# NLQHD-SATA_Rev_2.net
KiCad netlist of a schematic drawn in EAGLE
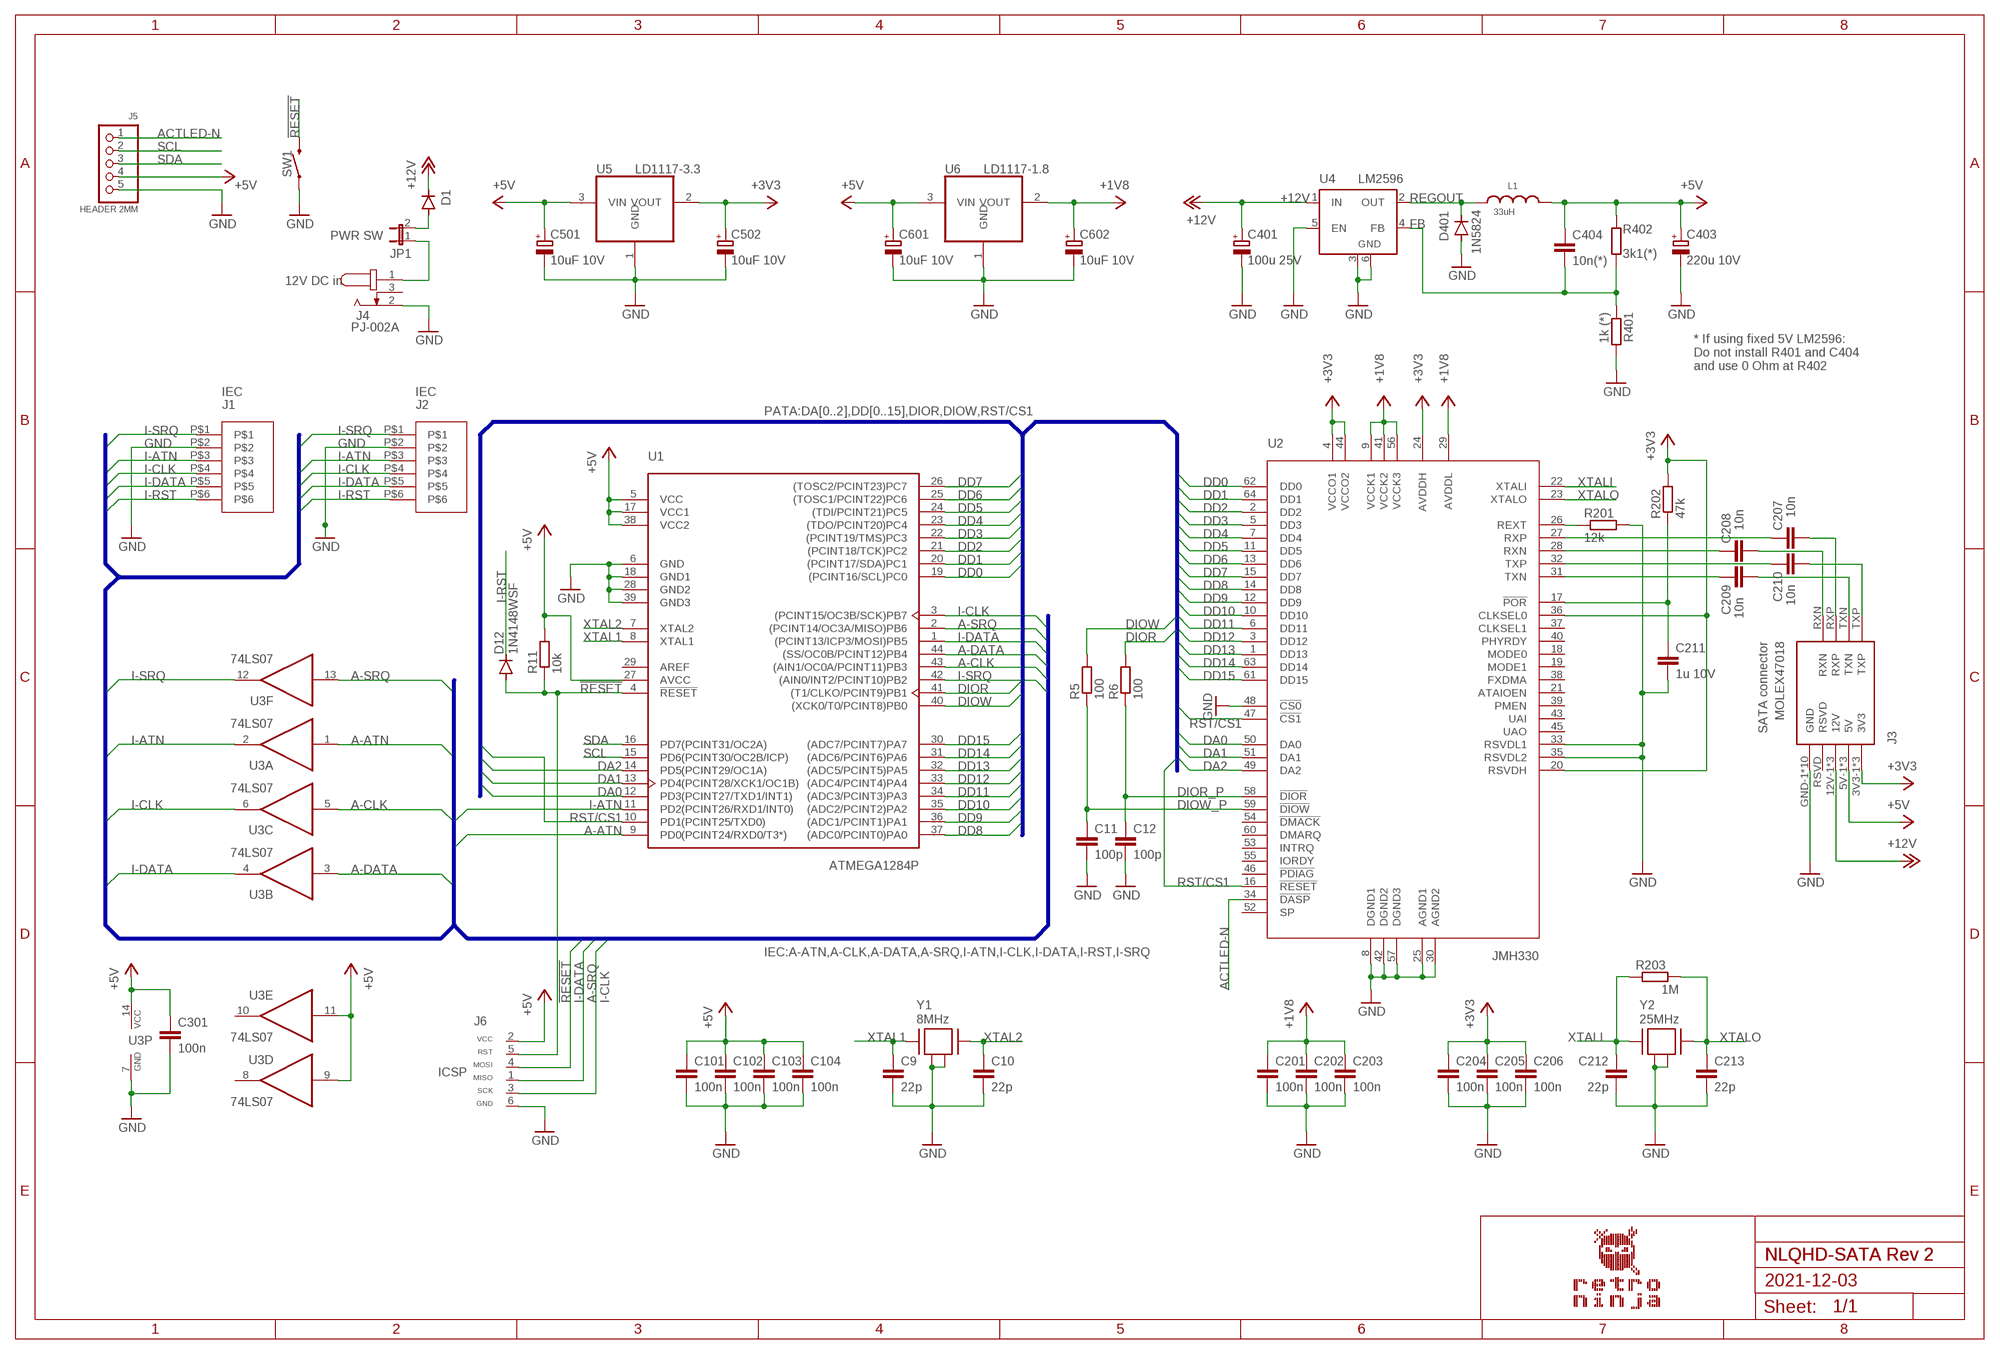
[diagram p0: schematic, sheet 1]

(export (version "E")
  (design (tool "Eeschema 10.0.6"))
  (components
    (comp (ref "C9")
      (value "22p")
      (footprint "eagle-import:C0805")
      (libsource (lib "eagle-import") (part "C-EUC0805"))
    )
    (comp (ref "C10")
      (value "22p")
      (footprint "eagle-import:C0805")
      (libsource (lib "eagle-import") (part "C-EUC0805"))
    )
    (comp (ref "C11")
      (value "100p")
      (footprint "eagle-import:C0805")
      (libsource (lib "eagle-import") (part "C-EUC0805"))
    )
    (comp (ref "C12")
      (value "100p")
      (footprint "eagle-import:C0805")
      (libsource (lib "eagle-import") (part "C-EUC0805"))
    )
    (comp (ref "C101")
      (value "100n")
      (footprint "eagle-import:C0805")
      (libsource (lib "eagle-import") (part "C-EUC0805"))
    )
    (comp (ref "C102")
      (value "100n")
      (footprint "eagle-import:C0805")
      (libsource (lib "eagle-import") (part "C-EUC0805"))
    )
    (comp (ref "C103")
      (value "100n")
      (footprint "eagle-import:C0805")
      (libsource (lib "eagle-import") (part "C-EUC0805"))
    )
    (comp (ref "C104")
      (value "100n")
      (footprint "eagle-import:C0805")
      (libsource (lib "eagle-import") (part "C-EUC0805"))
    )
    (comp (ref "C201")
      (value "100n")
      (footprint "eagle-import:C0805")
      (libsource (lib "eagle-import") (part "C-EUC0805"))
    )
    (comp (ref "C202")
      (value "100n")
      (footprint "eagle-import:C0805")
      (libsource (lib "eagle-import") (part "C-EUC0805"))
    )
    (comp (ref "C203")
      (value "100n")
      (footprint "eagle-import:C0805")
      (libsource (lib "eagle-import") (part "C-EUC0805"))
    )
    (comp (ref "C204")
      (value "100n")
      (footprint "eagle-import:C0805")
      (libsource (lib "eagle-import") (part "C-EUC0805"))
    )
    (comp (ref "C205")
      (value "100n")
      (footprint "eagle-import:C0805")
      (libsource (lib "eagle-import") (part "C-EUC0805"))
    )
    (comp (ref "C206")
      (value "100n")
      (footprint "eagle-import:C0805")
      (libsource (lib "eagle-import") (part "C-EUC0805"))
    )
    (comp (ref "C207")
      (value "10n")
      (footprint "eagle-import:C0805")
      (libsource (lib "eagle-import") (part "C-EUC0805"))
    )
    (comp (ref "C208")
      (value "10n")
      (footprint "eagle-import:C0805")
      (libsource (lib "eagle-import") (part "C-EUC0805"))
    )
    (comp (ref "C209")
      (value "10n")
      (footprint "eagle-import:C0805")
      (libsource (lib "eagle-import") (part "C-EUC0805"))
    )
    (comp (ref "C210")
      (value "10n")
      (footprint "eagle-import:C0805")
      (libsource (lib "eagle-import") (part "C-EUC0805"))
    )
    (comp (ref "C211")
      (value "1u 10V")
      (footprint "eagle-import:C0805")
      (libsource (lib "eagle-import") (part "C-EUC0805"))
    )
    (comp (ref "C212")
      (value "22p")
      (footprint "eagle-import:C0805")
      (libsource (lib "eagle-import") (part "C-EUC0805"))
    )
    (comp (ref "C213")
      (value "22p")
      (footprint "eagle-import:C0805")
      (libsource (lib "eagle-import") (part "C-EUC0805"))
    )
    (comp (ref "C301")
      (value "100n")
      (footprint "eagle-import:C0805")
      (libsource (lib "eagle-import") (part "C-EUC0805"))
    )
    (comp (ref "C401")
      (value "100u 25V")
      (footprint "eagle-import:CAP_POL_SMD_6.3X7.7")
      (libsource (lib "eagle-import") (part "CAPACITOR_POL_SMD_6.3X7.7"))
    )
    (comp (ref "C403")
      (value "220u 10V")
      (footprint "eagle-import:CAP_POL_SMD_6.3X7.7")
      (libsource (lib "eagle-import") (part "CAPACITOR_POL_SMD_6.3X7.7"))
    )
    (comp (ref "C404")
      (value "10n(*)")
      (footprint "eagle-import:C0805")
      (libsource (lib "eagle-import") (part "C-EUC0805"))
    )
    (comp (ref "C501")
      (value "10uF 10V")
      (footprint "eagle-import:A_3216-18R")
      (libsource (lib "eagle-import") (part "CPOL-EUA/3216-18R"))
    )
    (comp (ref "C502")
      (value "10uF 10V")
      (footprint "eagle-import:A_3216-18R")
      (libsource (lib "eagle-import") (part "CPOL-EUA/3216-18R"))
    )
    (comp (ref "C601")
      (value "10uF 10V")
      (footprint "eagle-import:A_3216-18R")
      (libsource (lib "eagle-import") (part "CPOL-EUA/3216-18R"))
    )
    (comp (ref "C602")
      (value "10uF 10V")
      (footprint "eagle-import:A_3216-18R")
      (libsource (lib "eagle-import") (part "CPOL-EUA/3216-18R"))
    )
    (comp (ref "D1")
      (value "DIODE_SOD-123FL")
      (footprint "eagle-import:SOD-123FL")
      (libsource (lib "eagle-import") (part "DIODE_SOD-123FL"))
    )
    (comp (ref "D12")
      (value "1N4148WSF")
      (footprint "eagle-import:SOD-323F")
      (libsource (lib "eagle-import") (part "DIODE_SOD-323F"))
    )
    (comp (ref "D401")
      (value "1N5824")
      (footprint "eagle-import:SOD-123FL")
      (libsource (lib "eagle-import") (part "DIODE_SOD-123FL"))
    )
    (comp (ref "J1")
      (value "DIN-6_PCB")
      (footprint "eagle-import:DIN-6-PCB")
      (libsource (lib "eagle-import") (part "DIN-6_PCB"))
    )
    (comp (ref "J2")
      (value "DIN-6_PCB")
      (footprint "eagle-import:DIN-6-PCB")
      (libsource (lib "eagle-import") (part "DIN-6_PCB"))
    )
    (comp (ref "J3")
      (value "MOLEX47018")
      (footprint "eagle-import:MOLEX47018SATA")
      (libsource (lib "eagle-import") (part "MOLEX47018SATA"))
    )
    (comp (ref "J4")
      (value "PJ-002A")
      (footprint "eagle-import:CUI_PJ-002A")
      (fields (field (name "MANUFACTURER") "CUI INC"))
      (libsource (lib "eagle-import") (part "PJ-002A"))
    )
    (comp (ref "J5")
      (value "HEADER 2MM")
      (footprint "eagle-import:HEADER_1X5_2MM_JST")
      (libsource (lib "eagle-import") (part "HEADER_1X5_2MM_JST"))
    )
    (comp (ref "J6")
      (value "ICSP_CONNECTOR_6_ALT")
      (footprint "eagle-import:HEADER_2X3_ALT")
      (libsource (lib "eagle-import") (part "ICSP_CONNECTOR_6_ALT"))
    )
    (comp (ref "JP1")
      (value "JUMPER-2")
      (footprint "eagle-import:HEADER_1X2")
      (libsource (lib "eagle-import") (part "JUMPER-2"))
    )
    (comp (ref "L1")
      (value "33uH")
      (footprint "eagle-import:WE-LHMI_1040")
      (libsource (lib "eagle-import") (part "WE-LHMI_1040_74437368330"))
    )
    (comp (ref "R5")
      (value "100")
      (footprint "eagle-import:R0805")
      (libsource (lib "eagle-import") (part "R-EU_R0805"))
    )
    (comp (ref "R6")
      (value "100")
      (footprint "eagle-import:R0805")
      (libsource (lib "eagle-import") (part "R-EU_R0805"))
    )
    (comp (ref "R11")
      (value "10k")
      (footprint "eagle-import:R0805")
      (libsource (lib "eagle-import") (part "R-EU_R0805"))
    )
    (comp (ref "R201")
      (value "12k")
      (footprint "eagle-import:R0805")
      (libsource (lib "eagle-import") (part "R-EU_R0805"))
    )
    (comp (ref "R202")
      (value "47k")
      (footprint "eagle-import:R0805")
      (libsource (lib "eagle-import") (part "R-EU_R0805"))
    )
    (comp (ref "R203")
      (value "1M")
      (footprint "eagle-import:R0805")
      (libsource (lib "eagle-import") (part "R-EU_R0805"))
    )
    (comp (ref "R401")
      (value "1k (*)")
      (footprint "eagle-import:R0805")
      (libsource (lib "eagle-import") (part "R-EU_R0805"))
    )
    (comp (ref "R402")
      (value "3k1(*)")
      (footprint "eagle-import:R0805")
      (libsource (lib "eagle-import") (part "R-EU_R0805"))
    )
    (comp (ref "SW1")
      (value "SWITCH_MOMENTARY_6.0X5.0_RIGHT_ANGLE")
      (footprint "eagle-import:SWITCH_MOM_6.0MMX5.0MM_RIGHT_ANGLE")
      (libsource (lib "eagle-import") (part "SWITCH_MOMENTARY_6.0X5.0_RIGHT_ANGLE"))
    )
    (comp (ref "U1")
      (value "ATMEGA1284P")
      (footprint "eagle-import:TQFP-44")
      (fields
        (field (name "DIGIKEY_PART_NUMBER") "ATMEGA1284P-AU-ND")
        (field (name "MANUFACTURER") "Microchip Technology")
        (field (name "MPN") "ATMEGA1284P-AU")
        (field (name "CREATED_BY") "PCBLayout.com")
      )
      (libsource (lib "eagle-import") (part "ATMEGA1284P-AU"))
    )
    (comp (ref "U2")
      (value "JMH330")
      (footprint "eagle-import:TQFP-64_12X12X1.20")
      (libsource (lib "eagle-import") (part "JMH330"))
    )
    (comp (ref "U3")
      (value "74LS07")
      (footprint "eagle-import:SOIC14")
      (libsource (lib "eagle-import") (part "7407_SOIC14"))
    )
    (comp (ref "U4")
      (value "LM2596")
      (footprint "eagle-import:TO263-5")
      (libsource (lib "eagle-import") (part "LM2596S"))
    )
    (comp (ref "U5")
      (value "LD1117-3.3")
      (footprint "eagle-import:SOT223")
      (fields (field (name "MF") "TEXAS INSTRUMENTS") (field (name "MPN") "REG1117FAKTTT"))
      (libsource (lib "eagle-import") (part "LD1117"))
    )
    (comp (ref "U6")
      (value "LD1117-1.8")
      (footprint "eagle-import:SOT223")
      (fields (field (name "MF") "TEXAS INSTRUMENTS") (field (name "MPN") "REG1117FAKTTT"))
      (libsource (lib "eagle-import") (part "LD1117"))
    )
    (comp (ref "Y1")
      (value "8MHz")
      (footprint "eagle-import:ECX-32")
      (libsource (lib "eagle-import") (part "ECX-32"))
    )
    (comp (ref "Y2")
      (value "25MHz")
      (footprint "eagle-import:ECX-32")
      (libsource (lib "eagle-import") (part "ECX-32"))
    )
  )
  (nets
    (net (code "2") (name "+1V8") (class "Default")
      (node (ref "C201") (pin "1") (pinfunction "1_1") (pintype "passive"))
      (node (ref "C202") (pin "1") (pinfunction "1_1") (pintype "passive"))
      (node (ref "C203") (pin "1") (pinfunction "1_1") (pintype "passive"))
      (node (ref "C602") (pin "+") (pinfunction "+_+") (pintype "passive"))
      (node (ref "U2") (pin "29") (pinfunction "AVDDL_29") (pintype "power_in"))
      (node (ref "U2") (pin "41") (pinfunction "VCCK2_41") (pintype "power_in"))
      (node (ref "U2") (pin "56") (pinfunction "VCCK3_56") (pintype "power_in"))
      (node (ref "U2") (pin "9") (pinfunction "VCCK1_9") (pintype "power_in"))
      (node (ref "U6") (pin "2") (pinfunction "VOUT_2") (pintype "output"))
    )
    (net (code "3") (name "+3V3") (class "Default")
      (node (ref "C204") (pin "1") (pinfunction "1_1") (pintype "passive"))
      (node (ref "C205") (pin "1") (pinfunction "1_1") (pintype "passive"))
      (node (ref "C206") (pin "1") (pinfunction "1_1") (pintype "passive"))
      (node (ref "C502") (pin "+") (pinfunction "+_+") (pintype "passive"))
      (node (ref "J3") (pin "3V3-1") (pinfunction "3V3_3V3-1") (pintype "power_in"))
      (node (ref "J3") (pin "3V3-2") (pinfunction "3V3_3V3-2") (pintype "power_in"))
      (node (ref "J3") (pin "3V3-3") (pinfunction "3V3_3V3-3") (pintype "power_in"))
      (node (ref "R202") (pin "2") (pinfunction "2_2") (pintype "passive"))
      (node (ref "U2") (pin "20") (pinfunction "RSVDH_20") (pintype "input"))
      (node (ref "U2") (pin "24") (pinfunction "AVDDH_24") (pintype "power_in"))
      (node (ref "U2") (pin "36") (pinfunction "CLKSEL0_36") (pintype "input"))
      (node (ref "U2") (pin "4") (pinfunction "VCCO1_4") (pintype "power_in"))
      (node (ref "U2") (pin "44") (pinfunction "VCCO2_44") (pintype "power_in"))
      (node (ref "U5") (pin "2") (pinfunction "VOUT_2") (pintype "output"))
    )
    (net (code "4") (name "+5V") (class "Default")
      (node (ref "C101") (pin "1") (pinfunction "1_1") (pintype "passive"))
      (node (ref "C102") (pin "1") (pinfunction "1_1") (pintype "passive"))
      (node (ref "C103") (pin "1") (pinfunction "1_1") (pintype "passive"))
      (node (ref "C104") (pin "1") (pinfunction "1_1") (pintype "passive"))
      (node (ref "C301") (pin "1") (pinfunction "1_1") (pintype "passive"))
      (node (ref "C403") (pin "+") (pinfunction "+_+") (pintype "passive"))
      (node (ref "C404") (pin "1") (pinfunction "1_1") (pintype "passive"))
      (node (ref "C501") (pin "+") (pinfunction "+_+") (pintype "passive"))
      (node (ref "C601") (pin "+") (pinfunction "+_+") (pintype "passive"))
      (node (ref "J3") (pin "5V-1") (pinfunction "5V_5V-1") (pintype "power_in"))
      (node (ref "J3") (pin "5V-2") (pinfunction "5V_5V-2") (pintype "power_in"))
      (node (ref "J3") (pin "5V-3") (pinfunction "5V_5V-3") (pintype "power_in"))
      (node (ref "J5") (pin "4") (pinfunction "4_4") (pintype "passive"))
      (node (ref "J6") (pin "2") (pinfunction "VCC_2") (pintype "power_in"))
      (node (ref "L1") (pin "2") (pinfunction "2_2") (pintype "passive"))
      (node (ref "R11") (pin "2") (pinfunction "2_2") (pintype "passive"))
      (node (ref "R402") (pin "2") (pinfunction "2_2") (pintype "passive"))
      (node (ref "U1") (pin "17") (pinfunction "VCC1_17") (pintype "power_in"))
      (node (ref "U1") (pin "27") (pinfunction "AVCC_27") (pintype "power_in"))
      (node (ref "U1") (pin "38") (pinfunction "VCC2_38") (pintype "power_in"))
      (node (ref "U1") (pin "5") (pinfunction "VCC_5") (pintype "power_in"))
      (node (ref "U3") (pin "11") (pinfunction "I_11") (pintype "input"))
      (node (ref "U3") (pin "14") (pinfunction "VCC_14") (pintype "power_in"))
      (node (ref "U3") (pin "9") (pinfunction "I_9") (pintype "input"))
      (node (ref "U5") (pin "3") (pinfunction "VIN_3") (pintype "input"))
      (node (ref "U6") (pin "3") (pinfunction "VIN_3") (pintype "input"))
    )
    (net (code "5") (name "+12V") (class "Default")
      (node (ref "C401") (pin "+") (pinfunction "+_+") (pintype "passive"))
      (node (ref "D1") (pin "C") (pinfunction "C_C") (pintype "passive"))
      (node (ref "J3") (pin "12V-1") (pinfunction "12V_12V-1") (pintype "power_in"))
      (node (ref "J3") (pin "12V-2") (pinfunction "12V_12V-2") (pintype "power_in"))
      (node (ref "J3") (pin "12V-3") (pinfunction "12V_12V-3") (pintype "power_in"))
      (node (ref "U4") (pin "1") (pinfunction "IN_1") (pintype "input"))
    )
    (net (code "6") (name "/A-ATN") (class "Default")
      (node (ref "U1") (pin "9") (pinfunction "PD0(PCINT24/RXD0/T3*)_9") (pintype "bidirectional"))
      (node (ref "U3") (pin "1") (pinfunction "I_1") (pintype "input"))
    )
    (net (code "7") (name "/A-CLK") (class "Default")
      (node (ref "U1") (pin "43") (pinfunction "(AIN1/OC0A/PCINT11)PB3_43") (pintype "bidirectional"))
      (node (ref "U3") (pin "5") (pinfunction "I_5") (pintype "input"))
    )
    (net (code "8") (name "/A-DATA") (class "Default")
      (node (ref "U1") (pin "44") (pinfunction "(SS/OC0B/PCINT12)PB4_44") (pintype "bidirectional"))
      (node (ref "U3") (pin "3") (pinfunction "I_3") (pintype "input"))
    )
    (net (code "9") (name "/A-SRQ") (class "Default")
      (node (ref "J6") (pin "1") (pinfunction "MISO_1") (pintype "output"))
      (node (ref "U1") (pin "2") (pinfunction "(PCINT14/OC3A/MISO)PB6_2") (pintype "bidirectional"))
      (node (ref "U3") (pin "13") (pinfunction "I_13") (pintype "input"))
    )
    (net (code "10") (name "/ACTLED-N") (class "Default")
      (node (ref "J5") (pin "1") (pinfunction "1_1") (pintype "passive"))
      (node (ref "U2") (pin "34") (pinfunction "~{DASP}_34") (pintype "bidirectional"))
    )
    (net (code "11") (name "/DA0") (class "Default")
      (node (ref "U1") (pin "12") (pinfunction "PD3(PCINT27/TXD1/INT1)_12") (pintype "bidirectional"))
      (node (ref "U2") (pin "50") (pinfunction "DA0_50") (pintype "bidirectional"))
    )
    (net (code "12") (name "/DA1") (class "Default")
      (node (ref "U1") (pin "13") (pinfunction "PD4(PCINT28/XCK1/OC1B)_13") (pintype "bidirectional"))
      (node (ref "U2") (pin "51") (pinfunction "DA1_51") (pintype "bidirectional"))
    )
    (net (code "13") (name "/DA2") (class "Default")
      (node (ref "U1") (pin "14") (pinfunction "PD5(PCINT29/OC1A)_14") (pintype "bidirectional"))
      (node (ref "U2") (pin "49") (pinfunction "DA2_49") (pintype "bidirectional"))
    )
    (net (code "14") (name "/DD0") (class "Default")
      (node (ref "U1") (pin "19") (pinfunction "(PCINT16/SCL)PC0_19") (pintype "bidirectional"))
      (node (ref "U2") (pin "62") (pinfunction "DD0_62") (pintype "bidirectional"))
    )
    (net (code "15") (name "/DD1") (class "Default")
      (node (ref "U1") (pin "20") (pinfunction "(PCINT17/SDA)PC1_20") (pintype "bidirectional"))
      (node (ref "U2") (pin "64") (pinfunction "DD1_64") (pintype "bidirectional"))
    )
    (net (code "16") (name "/DD2") (class "Default")
      (node (ref "U1") (pin "21") (pinfunction "(PCINT18/TCK)PC2_21") (pintype "bidirectional"))
      (node (ref "U2") (pin "2") (pinfunction "DD2_2") (pintype "bidirectional"))
    )
    (net (code "17") (name "/DD3") (class "Default")
      (node (ref "U1") (pin "22") (pinfunction "(PCINT19/TMS)PC3_22") (pintype "bidirectional"))
      (node (ref "U2") (pin "5") (pinfunction "DD3_5") (pintype "bidirectional"))
    )
    (net (code "18") (name "/DD4") (class "Default")
      (node (ref "U1") (pin "23") (pinfunction "(TDO/PCINT20)PC4_23") (pintype "bidirectional"))
      (node (ref "U2") (pin "7") (pinfunction "DD4_7") (pintype "bidirectional"))
    )
    (net (code "19") (name "/DD5") (class "Default")
      (node (ref "U1") (pin "24") (pinfunction "(TDI/PCINT21)PC5_24") (pintype "bidirectional"))
      (node (ref "U2") (pin "11") (pinfunction "DD5_11") (pintype "bidirectional"))
    )
    (net (code "20") (name "/DD6") (class "Default")
      (node (ref "U1") (pin "25") (pinfunction "(TOSC1/PCINT22)PC6_25") (pintype "bidirectional"))
      (node (ref "U2") (pin "13") (pinfunction "DD6_13") (pintype "bidirectional"))
    )
    (net (code "21") (name "/DD7") (class "Default")
      (node (ref "U1") (pin "26") (pinfunction "(TOSC2/PCINT23)PC7_26") (pintype "bidirectional"))
      (node (ref "U2") (pin "15") (pinfunction "DD7_15") (pintype "bidirectional"))
    )
    (net (code "22") (name "/DD8") (class "Default")
      (node (ref "U1") (pin "37") (pinfunction "(ADC0/PCINT0)PA0_37") (pintype "bidirectional"))
      (node (ref "U2") (pin "14") (pinfunction "DD8_14") (pintype "bidirectional"))
    )
    (net (code "23") (name "/DD9") (class "Default")
      (node (ref "U1") (pin "36") (pinfunction "(ADC1/PCINT1)PA1_36") (pintype "bidirectional"))
      (node (ref "U2") (pin "12") (pinfunction "DD9_12") (pintype "bidirectional"))
    )
    (net (code "24") (name "/DD10") (class "Default")
      (node (ref "U1") (pin "35") (pinfunction "(ADC2/PCINT2)PA2_35") (pintype "bidirectional"))
      (node (ref "U2") (pin "10") (pinfunction "DD10_10") (pintype "bidirectional"))
    )
    (net (code "25") (name "/DD11") (class "Default")
      (node (ref "U1") (pin "34") (pinfunction "(ADC3/PCINT3)PA3_34") (pintype "bidirectional"))
      (node (ref "U2") (pin "6") (pinfunction "DD11_6") (pintype "bidirectional"))
    )
    (net (code "26") (name "/DD12") (class "Default")
      (node (ref "U1") (pin "33") (pinfunction "(ADC4/PCINT4)PA4_33") (pintype "bidirectional"))
      (node (ref "U2") (pin "3") (pinfunction "DD12_3") (pintype "bidirectional"))
    )
    (net (code "27") (name "/DD13") (class "Default")
      (node (ref "U1") (pin "32") (pinfunction "(ADC5/PCINT5)PA5_32") (pintype "bidirectional"))
      (node (ref "U2") (pin "1") (pinfunction "DD13_1") (pintype "bidirectional"))
    )
    (net (code "28") (name "/DD14") (class "Default")
      (node (ref "U1") (pin "31") (pinfunction "(ADC6/PCINT6)PA6_31") (pintype "bidirectional"))
      (node (ref "U2") (pin "63") (pinfunction "DD14_63") (pintype "bidirectional"))
    )
    (net (code "29") (name "/DD15") (class "Default")
      (node (ref "U1") (pin "30") (pinfunction "(ADC7/PCINT7)PA7_30") (pintype "bidirectional"))
      (node (ref "U2") (pin "61") (pinfunction "DD15_61") (pintype "bidirectional"))
    )
    (net (code "30") (name "/DIOR") (class "Default")
      (node (ref "R6") (pin "2") (pinfunction "2_2") (pintype "passive"))
      (node (ref "U1") (pin "41") (pinfunction "(T1/CLKO/PCINT9)PB1_41") (pintype "bidirectional"))
    )
    (net (code "31") (name "/DIOR_P") (class "Default")
      (node (ref "C12") (pin "1") (pinfunction "1_1") (pintype "passive"))
      (node (ref "R6") (pin "1") (pinfunction "1_1") (pintype "passive"))
      (node (ref "U2") (pin "58") (pinfunction "~{DIOR}_58") (pintype "bidirectional"))
    )
    (net (code "32") (name "/DIOW") (class "Default")
      (node (ref "R5") (pin "2") (pinfunction "2_2") (pintype "passive"))
      (node (ref "U1") (pin "40") (pinfunction "(XCK0/T0/PCINT8)PB0_40") (pintype "bidirectional"))
    )
    (net (code "33") (name "/DIOW_P") (class "Default")
      (node (ref "C11") (pin "1") (pinfunction "1_1") (pintype "passive"))
      (node (ref "R5") (pin "1") (pinfunction "1_1") (pintype "passive"))
      (node (ref "U2") (pin "59") (pinfunction "~{DIOW}_59") (pintype "bidirectional"))
    )
    (net (code "34") (name "/FB") (class "Default")
      (node (ref "C404") (pin "2") (pinfunction "2_2") (pintype "passive"))
      (node (ref "R401") (pin "1") (pinfunction "1_1") (pintype "passive"))
      (node (ref "R402") (pin "1") (pinfunction "1_1") (pintype "passive"))
      (node (ref "U4") (pin "4") (pinfunction "FB_4") (pintype "input"))
    )
    (net (code "35") (name "/I-ATN") (class "Default")
      (node (ref "J1") (pin "P$3") (pinfunction "P$3_P$3") (pintype "bidirectional"))
      (node (ref "J2") (pin "P$3") (pinfunction "P$3_P$3") (pintype "bidirectional"))
      (node (ref "U1") (pin "11") (pinfunction "PD2(PCINT26/RXD1/INT0)_11") (pintype "bidirectional"))
      (node (ref "U3") (pin "2") (pinfunction "O_2") (pintype "open_collector"))
    )
    (net (code "36") (name "/I-CLK") (class "Default")
      (node (ref "J1") (pin "P$4") (pinfunction "P$4_P$4") (pintype "bidirectional"))
      (node (ref "J2") (pin "P$4") (pinfunction "P$4_P$4") (pintype "bidirectional"))
      (node (ref "J6") (pin "3") (pinfunction "SCK_3") (pintype "input"))
      (node (ref "U1") (pin "3") (pinfunction "(PCINT15/OC3B/SCK)PB7_3") (pintype "bidirectional"))
      (node (ref "U3") (pin "6") (pinfunction "O_6") (pintype "open_collector"))
    )
    (net (code "37") (name "/I-DATA") (class "Default")
      (node (ref "J1") (pin "P$5") (pinfunction "P$5_P$5") (pintype "bidirectional"))
      (node (ref "J2") (pin "P$5") (pinfunction "P$5_P$5") (pintype "bidirectional"))
      (node (ref "J6") (pin "4") (pinfunction "MOSI_4") (pintype "input"))
      (node (ref "U1") (pin "1") (pinfunction "(PCINT13/ICP3/MOSI)PB5_1") (pintype "bidirectional"))
      (node (ref "U3") (pin "4") (pinfunction "O_4") (pintype "open_collector"))
    )
    (net (code "38") (name "/I-RST") (class "Default")
      (node (ref "D12") (pin "C") (pinfunction "C_C") (pintype "passive"))
      (node (ref "J1") (pin "P$6") (pinfunction "P$6_P$6") (pintype "bidirectional"))
      (node (ref "J2") (pin "P$6") (pinfunction "P$6_P$6") (pintype "bidirectional"))
    )
    (net (code "39") (name "/I-SRQ") (class "Default")
      (node (ref "J1") (pin "P$1") (pinfunction "P$1_P$1") (pintype "bidirectional"))
      (node (ref "J2") (pin "P$1") (pinfunction "P$1_P$1") (pintype "bidirectional"))
      (node (ref "U1") (pin "42") (pinfunction "(AIN0/INT2/PCINT10)PB2_42") (pintype "bidirectional"))
      (node (ref "U3") (pin "12") (pinfunction "O_12") (pintype "open_collector"))
    )
    (net (code "40") (name "/REGOUT") (class "Default")
      (node (ref "D401") (pin "C") (pinfunction "C_C") (pintype "passive"))
      (node (ref "L1") (pin "1") (pinfunction "1_1") (pintype "passive"))
      (node (ref "U4") (pin "2") (pinfunction "OUT_2") (pintype "output"))
    )
    (net (code "41") (name "/RST{slash}CS1") (class "Default")
      (node (ref "U1") (pin "10") (pinfunction "PD1(PCINT25/TXD0)_10") (pintype "bidirectional"))
      (node (ref "U2") (pin "16") (pinfunction "~{RESET}_16") (pintype "bidirectional"))
      (node (ref "U2") (pin "47") (pinfunction "~{CS1}_47") (pintype "bidirectional"))
    )
    (net (code "42") (name "/SCL") (class "Default")
      (node (ref "J5") (pin "2") (pinfunction "2_2") (pintype "passive"))
      (node (ref "U1") (pin "15") (pinfunction "PD6(PCINT30/OC2B/ICP)_15") (pintype "bidirectional"))
    )
    (net (code "43") (name "/SDA") (class "Default")
      (node (ref "J5") (pin "3") (pinfunction "3_3") (pintype "passive"))
      (node (ref "U1") (pin "16") (pinfunction "PD7(PCINT31/OC2A)_16") (pintype "bidirectional"))
    )
    (net (code "44") (name "/XTAL1") (class "Default")
      (node (ref "C9") (pin "1") (pinfunction "1_1") (pintype "passive"))
      (node (ref "U1") (pin "8") (pinfunction "XTAL1_8") (pintype "input"))
      (node (ref "Y1") (pin "1") (pinfunction "1_1") (pintype "passive"))
    )
    (net (code "45") (name "/XTAL2") (class "Default")
      (node (ref "C10") (pin "1") (pinfunction "1_1") (pintype "passive"))
      (node (ref "U1") (pin "7") (pinfunction "XTAL2_7") (pintype "output"))
      (node (ref "Y1") (pin "3") (pinfunction "3_3") (pintype "passive"))
    )
    (net (code "46") (name "/XTALI") (class "Default")
      (node (ref "C212") (pin "1") (pinfunction "1_1") (pintype "passive"))
      (node (ref "R203") (pin "1") (pinfunction "1_1") (pintype "passive"))
      (node (ref "U2") (pin "22") (pinfunction "XTALI_22") (pintype "input"))
      (node (ref "Y2") (pin "1") (pinfunction "1_1") (pintype "passive"))
    )
    (net (code "47") (name "/XTALO") (class "Default")
      (node (ref "C213") (pin "1") (pinfunction "1_1") (pintype "passive"))
      (node (ref "R203") (pin "2") (pinfunction "2_2") (pintype "passive"))
      (node (ref "U2") (pin "23") (pinfunction "XTALO_23") (pintype "output"))
      (node (ref "Y2") (pin "3") (pinfunction "3_3") (pintype "passive"))
    )
    (net (code "50") (name "/~{RESET}") (class "Default")
      (node (ref "D12") (pin "A") (pinfunction "A_A") (pintype "passive"))
      (node (ref "J6") (pin "5") (pinfunction "RST_5") (pintype "input"))
      (node (ref "R11") (pin "1") (pinfunction "1_1") (pintype "passive"))
      (node (ref "SW1") (pin "2") (pinfunction "2_2") (pintype "passive"))
      (node (ref "U1") (pin "4") (pinfunction "~{RESET}_4") (pintype "input"))
    )
    (net (code "51") (name "GND") (class "Default")
      (node (ref "C10") (pin "2") (pinfunction "2_2") (pintype "passive"))
      (node (ref "C101") (pin "2") (pinfunction "2_2") (pintype "passive"))
      (node (ref "C102") (pin "2") (pinfunction "2_2") (pintype "passive"))
      (node (ref "C103") (pin "2") (pinfunction "2_2") (pintype "passive"))
      (node (ref "C104") (pin "2") (pinfunction "2_2") (pintype "passive"))
      (node (ref "C11") (pin "2") (pinfunction "2_2") (pintype "passive"))
      (node (ref "C12") (pin "2") (pinfunction "2_2") (pintype "passive"))
      (node (ref "C201") (pin "2") (pinfunction "2_2") (pintype "passive"))
      (node (ref "C202") (pin "2") (pinfunction "2_2") (pintype "passive"))
      (node (ref "C203") (pin "2") (pinfunction "2_2") (pintype "passive"))
      (node (ref "C204") (pin "2") (pinfunction "2_2") (pintype "passive"))
      (node (ref "C205") (pin "2") (pinfunction "2_2") (pintype "passive"))
      (node (ref "C206") (pin "2") (pinfunction "2_2") (pintype "passive"))
      (node (ref "C211") (pin "2") (pinfunction "2_2") (pintype "passive"))
      (node (ref "C212") (pin "2") (pinfunction "2_2") (pintype "passive"))
      (node (ref "C213") (pin "2") (pinfunction "2_2") (pintype "passive"))
      (node (ref "C301") (pin "2") (pinfunction "2_2") (pintype "passive"))
      (node (ref "C401") (pin "-") (pinfunction "-_-") (pintype "passive"))
      (node (ref "C403") (pin "-") (pinfunction "-_-") (pintype "passive"))
      (node (ref "C501") (pin "-") (pinfunction "-_-") (pintype "passive"))
      (node (ref "C502") (pin "-") (pinfunction "-_-") (pintype "passive"))
      (node (ref "C601") (pin "-") (pinfunction "-_-") (pintype "passive"))
      (node (ref "C602") (pin "-") (pinfunction "-_-") (pintype "passive"))
      (node (ref "C9") (pin "2") (pinfunction "2_2") (pintype "passive"))
      (node (ref "D401") (pin "A") (pinfunction "A_A") (pintype "passive"))
      (node (ref "J1") (pin "P$2") (pinfunction "P$2_P$2") (pintype "bidirectional"))
      (node (ref "J2") (pin "P$2") (pinfunction "P$2_P$2") (pintype "bidirectional"))
      (node (ref "J3") (pin "GND-1") (pinfunction "GND_GND-1") (pintype "power_in"))
      (node (ref "J3") (pin "GND-10") (pinfunction "GND_GND-10") (pintype "power_in"))
      (node (ref "J3") (pin "GND-2") (pinfunction "GND_GND-2") (pintype "power_in"))
      (node (ref "J3") (pin "GND-3") (pinfunction "GND_GND-3") (pintype "power_in"))
      (node (ref "J3") (pin "GND-4") (pinfunction "GND_GND-4") (pintype "power_in"))
      (node (ref "J3") (pin "GND-5") (pinfunction "GND_GND-5") (pintype "power_in"))
      (node (ref "J3") (pin "GND-6") (pinfunction "GND_GND-6") (pintype "power_in"))
      (node (ref "J3") (pin "GND-7") (pinfunction "GND_GND-7") (pintype "power_in"))
      (node (ref "J3") (pin "GND-8") (pinfunction "GND_GND-8") (pintype "power_in"))
      (node (ref "J3") (pin "GND-9") (pinfunction "GND_GND-9") (pintype "power_in"))
      (node (ref "J4") (pin "2") (pinfunction "2_2") (pintype "passive"))
      (node (ref "J5") (pin "5") (pinfunction "5_5") (pintype "passive"))
      (node (ref "J6") (pin "6") (pinfunction "GND_6") (pintype "power_in"))
      (node (ref "R201") (pin "2") (pinfunction "2_2") (pintype "passive"))
      (node (ref "R401") (pin "2") (pinfunction "2_2") (pintype "passive"))
      (node (ref "SW1") (pin "1") (pinfunction "1_1") (pintype "passive"))
      (node (ref "U1") (pin "18") (pinfunction "GND1_18") (pintype "power_in"))
      (node (ref "U1") (pin "28") (pinfunction "GND2_28") (pintype "power_in"))
      (node (ref "U1") (pin "39") (pinfunction "GND3_39") (pintype "power_in"))
      (node (ref "U1") (pin "6") (pinfunction "GND_6") (pintype "power_in"))
      (node (ref "U2") (pin "25") (pinfunction "AGND1_25") (pintype "power_in"))
      (node (ref "U2") (pin "30") (pinfunction "AGND2_30") (pintype "power_in"))
      (node (ref "U2") (pin "33") (pinfunction "RSVDL1_33") (pintype "input"))
      (node (ref "U2") (pin "35") (pinfunction "RSVDL2_35") (pintype "input"))
      (node (ref "U2") (pin "42") (pinfunction "DGND2_42") (pintype "power_in"))
      (node (ref "U2") (pin "48") (pinfunction "~{CS0}_48") (pintype "bidirectional"))
      (node (ref "U2") (pin "57") (pinfunction "DGND3_57") (pintype "power_in"))
      (node (ref "U2") (pin "8") (pinfunction "DGND1_8") (pintype "power_in"))
      (node (ref "U3") (pin "7") (pinfunction "GND_7") (pintype "power_in"))
      (node (ref "U4") (pin "3") (pinfunction "GND_3") (pintype "power_in"))
      (node (ref "U4") (pin "5") (pinfunction "EN_5") (pintype "input"))
      (node (ref "U4") (pin "6") (pinfunction "GND_6") (pintype "power_in"))
      (node (ref "U5") (pin "1") (pinfunction "GND_1") (pintype "power_in"))
      (node (ref "U6") (pin "1") (pinfunction "GND_1") (pintype "power_in"))
      (node (ref "Y1") (pin "2") (pinfunction "2_2") (pintype "passive"))
      (node (ref "Y1") (pin "4") (pinfunction "4_4") (pintype "passive"))
      (node (ref "Y2") (pin "2") (pinfunction "2_2") (pintype "passive"))
      (node (ref "Y2") (pin "4") (pinfunction "4_4") (pintype "passive"))
    )
    (net (code "52") (name "Net-(C207-Pad2)") (class "Default")
      (node (ref "C207") (pin "2") (pinfunction "2_2") (pintype "passive"))
      (node (ref "J3") (pin "RXP") (pinfunction "RXP_RXP") (pintype "bidirectional"))
    )
    (net (code "53") (name "Net-(C208-Pad2)") (class "Default")
      (node (ref "C208") (pin "2") (pinfunction "2_2") (pintype "passive"))
      (node (ref "J3") (pin "RXN") (pinfunction "RXN_RXN") (pintype "bidirectional"))
    )
    (net (code "54") (name "Net-(C209-Pad2)") (class "Default")
      (node (ref "C209") (pin "2") (pinfunction "2_2") (pintype "passive"))
      (node (ref "J3") (pin "TXN") (pinfunction "TXN_TXN") (pintype "bidirectional"))
    )
    (net (code "55") (name "Net-(C210-Pad2)") (class "Default")
      (node (ref "C210") (pin "2") (pinfunction "2_2") (pintype "passive"))
      (node (ref "J3") (pin "TXP") (pinfunction "TXP_TXP") (pintype "bidirectional"))
    )
    (net (code "56") (name "Net-(D1-PadA)") (class "Default")
      (node (ref "D1") (pin "A") (pinfunction "A_A") (pintype "passive"))
      (node (ref "JP1") (pin "2") (pinfunction "2_2") (pintype "passive"))
    )
    (net (code "57") (name "Net-(J4-Pad1)") (class "Default")
      (node (ref "J4") (pin "1") (pinfunction "1_1") (pintype "passive"))
      (node (ref "JP1") (pin "1") (pinfunction "1_1") (pintype "passive"))
    )
    (net (code "58") (name "Net-(U2-REXT)") (class "Default")
      (node (ref "R201") (pin "1") (pinfunction "1_1") (pintype "passive"))
      (node (ref "U2") (pin "26") (pinfunction "REXT_26") (pintype "input"))
    )
    (net (code "59") (name "Net-(U2-RXN)") (class "Default")
      (node (ref "C208") (pin "1") (pinfunction "1_1") (pintype "passive"))
      (node (ref "U2") (pin "28") (pinfunction "RXN_28") (pintype "input"))
    )
    (net (code "60") (name "Net-(U2-RXP)") (class "Default")
      (node (ref "C207") (pin "1") (pinfunction "1_1") (pintype "passive"))
      (node (ref "U2") (pin "27") (pinfunction "RXP_27") (pintype "input"))
    )
    (net (code "61") (name "Net-(U2-TXN)") (class "Default")
      (node (ref "C209") (pin "1") (pinfunction "1_1") (pintype "passive"))
      (node (ref "U2") (pin "31") (pinfunction "TXN_31") (pintype "output"))
    )
    (net (code "62") (name "Net-(U2-TXP)") (class "Default")
      (node (ref "C210") (pin "1") (pinfunction "1_1") (pintype "passive"))
      (node (ref "U2") (pin "32") (pinfunction "TXP_32") (pintype "output"))
    )
    (net (code "63") (name "Net-(U2-~{POR})") (class "Default")
      (node (ref "C211") (pin "1") (pinfunction "1_1") (pintype "passive"))
      (node (ref "R202") (pin "1") (pinfunction "1_1") (pintype "passive"))
      (node (ref "U2") (pin "17") (pinfunction "~{POR}_17") (pintype "input"))
    )
    (net (code "64") (name "unconnected-(J3-PadRSVD)") (class "Default")
      (node (ref "J3") (pin "RSVD") (pinfunction "RSVD_RSVD") (pintype "bidirectional"))
    )
    (net (code "65") (name "unconnected-(J4-Pad3)") (class "Default")
      (node (ref "J4") (pin "3") (pinfunction "3_3") (pintype "passive"))
    )
    (net (code "66") (name "unconnected-(U1-AREF-Pad29)") (class "Default")
      (node (ref "U1") (pin "29") (pinfunction "AREF_29") (pintype "input"))
    )
    (net (code "67") (name "unconnected-(U2-ATAIOEN-Pad21)") (class "Default")
      (node (ref "U2") (pin "21") (pinfunction "ATAIOEN_21") (pintype "input"))
    )
    (net (code "68") (name "unconnected-(U2-CLKSEL1-Pad37)") (class "Default")
      (node (ref "U2") (pin "37") (pinfunction "CLKSEL1_37") (pintype "input"))
    )
    (net (code "69") (name "unconnected-(U2-DMARQ-Pad60)") (class "Default")
      (node (ref "U2") (pin "60") (pinfunction "DMARQ_60") (pintype "bidirectional"))
    )
    (net (code "70") (name "unconnected-(U2-FXDMA-Pad38)") (class "Default")
      (node (ref "U2") (pin "38") (pinfunction "FXDMA_38") (pintype "input"))
    )
    (net (code "71") (name "unconnected-(U2-INTRQ-Pad53)") (class "Default")
      (node (ref "U2") (pin "53") (pinfunction "INTRQ_53") (pintype "bidirectional"))
    )
    (net (code "72") (name "unconnected-(U2-IORDY-Pad55)") (class "Default")
      (node (ref "U2") (pin "55") (pinfunction "IORDY_55") (pintype "bidirectional"))
    )
    (net (code "73") (name "unconnected-(U2-MODE0-Pad18)") (class "Default")
      (node (ref "U2") (pin "18") (pinfunction "MODE0_18") (pintype "input"))
    )
    (net (code "74") (name "unconnected-(U2-MODE1-Pad19)") (class "Default")
      (node (ref "U2") (pin "19") (pinfunction "MODE1_19") (pintype "input"))
    )
    (net (code "75") (name "unconnected-(U2-PHYRDY-Pad40)") (class "Default")
      (node (ref "U2") (pin "40") (pinfunction "PHYRDY_40") (pintype "output"))
    )
    (net (code "76") (name "unconnected-(U2-PMEN-Pad39)") (class "Default")
      (node (ref "U2") (pin "39") (pinfunction "PMEN_39") (pintype "input"))
    )
    (net (code "77") (name "unconnected-(U2-SP-Pad52)") (class "Default")
      (node (ref "U2") (pin "52") (pinfunction "SP_52") (pintype "no_connect"))
    )
    (net (code "78") (name "unconnected-(U2-UAI-Pad43)") (class "Default")
      (node (ref "U2") (pin "43") (pinfunction "UAI_43") (pintype "input"))
    )
    (net (code "79") (name "unconnected-(U2-UAO-Pad45)") (class "Default")
      (node (ref "U2") (pin "45") (pinfunction "UAO_45") (pintype "output"))
    )
    (net (code "80") (name "unconnected-(U2-~{DMACK}-Pad54)") (class "Default")
      (node (ref "U2") (pin "54") (pinfunction "~{DMACK}_54") (pintype "bidirectional"))
    )
    (net (code "81") (name "unconnected-(U2-~{PDIAG}-Pad46)") (class "Default")
      (node (ref "U2") (pin "46") (pinfunction "~{PDIAG}_46") (pintype "bidirectional"))
    )
    (net (code "82") (name "unconnected-(U3D-O-Pad8)") (class "Default")
      (node (ref "U3") (pin "8") (pinfunction "O_8") (pintype "open_collector"))
    )
    (net (code "83") (name "unconnected-(U3E-O-Pad10)") (class "Default")
      (node (ref "U3") (pin "10") (pinfunction "O_10") (pintype "open_collector"))
    )
  )
)
